# Team_Scheire_Maarten_00.net
KiCad netlist of a schematic drawn in Altium Designer
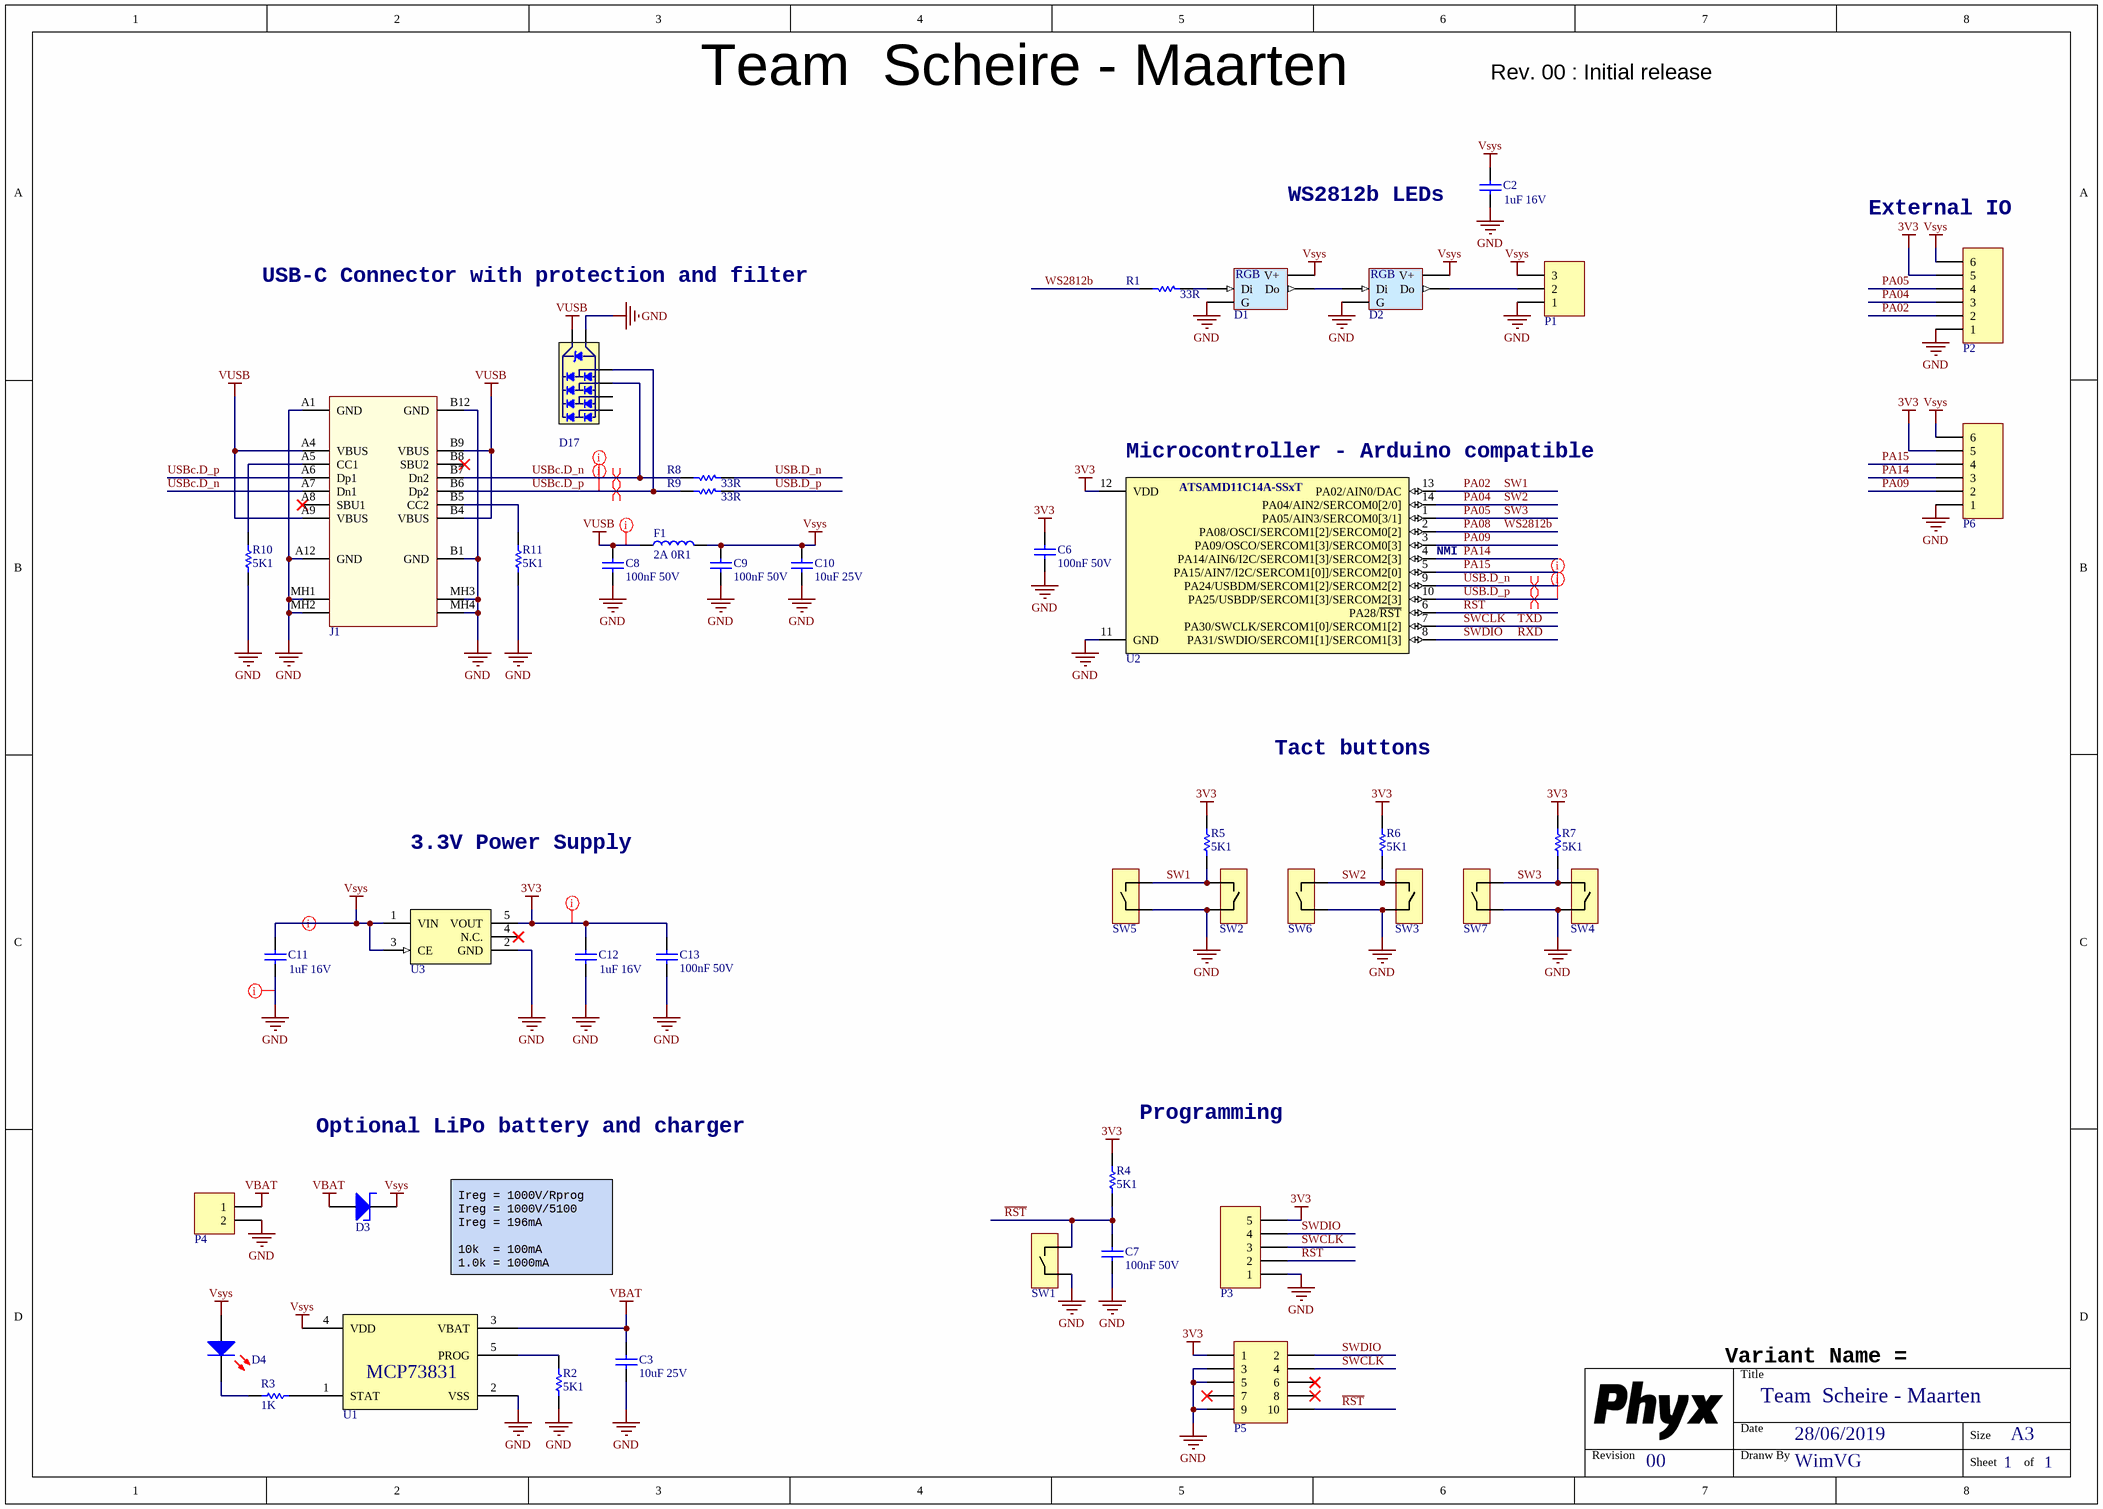
[diagram p0: Team_Scheire_Maarten_00.SchDoc]

(export (version "E")
  (design (tool "Eeschema 10.0.6"))
  (components
    (comp (ref "C2")
      (value "1uF 16V")
      (footprint "C0603_N")
      (description "Capacitor Ceramic")
      (fields (field (name "Comment") "CAP_CERAMIC"))
      (libsource (lib "Phyx_Components") (part "CAP_CERAMIC"))
    )
    (comp (ref "C3")
      (value "10uF 25V")
      (footprint "C1206_N")
      (description "CAP # 10uF 25V 1206")
      (fields (field (name "Comment") "CAP_CERAMIC"))
      (libsource (lib "Phyx_Components") (part "CAP_CERAMIC"))
    )
    (comp (ref "C6")
      (value "100nF 50V")
      (footprint "C0603_N")
      (description "CAP # 100nF 50V 0603")
      (fields (field (name "Comment") "CAP_CERAMIC"))
      (libsource (lib "Phyx_Components") (part "CAP_CERAMIC"))
    )
    (comp (ref "C7")
      (value "100nF 50V")
      (footprint "C0603_N")
      (description "CAP # 100nF 50V 0603")
      (fields (field (name "Comment") "CAP_CERAMIC"))
      (libsource (lib "Phyx_Components") (part "CAP_CERAMIC"))
    )
    (comp (ref "C8")
      (value "100nF 50V")
      (footprint "C0603_N")
      (description "CAP # 100nF 50V 0603")
      (fields (field (name "Comment") "CAP_CERAMIC"))
      (libsource (lib "Phyx_Components") (part "CAP_CERAMIC"))
    )
    (comp (ref "C9")
      (value "100nF 50V")
      (footprint "C0603_N")
      (description "CAP # 100nF 50V 0603")
      (fields (field (name "Comment") "CAP_CERAMIC"))
      (libsource (lib "Phyx_Components") (part "CAP_CERAMIC"))
    )
    (comp (ref "C10")
      (value "10uF 25V")
      (footprint "C1206_N")
      (description "CAP # 10uF 25V 1206")
      (fields (field (name "Comment") "CAP_CERAMIC"))
      (libsource (lib "Phyx_Components") (part "CAP_CERAMIC"))
    )
    (comp (ref "C11")
      (value "1uF 16V")
      (footprint "C0603_N")
      (description "Capacitor Ceramic")
      (fields (field (name "Comment") "CAP_CERAMIC"))
      (libsource (lib "Phyx_Components") (part "CAP_CERAMIC"))
    )
    (comp (ref "C12")
      (value "1uF 16V")
      (footprint "C0603_N")
      (description "Capacitor Ceramic")
      (fields (field (name "Comment") "CAP_CERAMIC"))
      (libsource (lib "Phyx_Components") (part "CAP_CERAMIC"))
    )
    (comp (ref "C13")
      (value "100nF 50V")
      (footprint "C0603_N")
      (description "CAP # 100nF 50V 0603")
      (fields (field (name "Comment") "CAP_CERAMIC"))
      (libsource (lib "Phyx_Components") (part "CAP_CERAMIC"))
    )
    (comp (ref "D1")
      (value "WS2812 based digital RGB LED 5050 Black package")
      (footprint "LED_5050_WS2812B_BLACK")
      (description "=Description")
      (libsource (lib "Phyx_Components") (part "LED_RGB_WS2812B_5050"))
    )
    (comp (ref "D2")
      (value "WS2812 based digital RGB LED 5050 Black package")
      (footprint "LED_5050_WS2812B_BLACK")
      (description "=Description")
      (libsource (lib "Phyx_Components") (part "LED_RGB_WS2812B_5050"))
    )
    (comp (ref "D3")
      (value "MBR0540T3G Schottky ULTRAFAST, 500MA, 40V")
      (footprint "ON_SOD-123FL")
      (description "=Description")
      (libsource (lib "Phyx_Components") (part "Schottky_21"))
    )
    (comp (ref "D4")
      (value "Default 0805 Red LED")
      (footprint "LED_0805_RD")
      (description "=Description")
      (libsource (lib "Phyx_Components") (part "LED_RED"))
    )
    (comp (ref "D17")
      (value "TVS Diode Dual USB")
      (footprint "NXP_SOT457")
      (description "TVS # IP4220CZ6 Dual USB")
      (libsource (lib "Phyx_Components") (part "NXP_IP4220CZ6"))
    )
    (comp (ref "F1")
      (value "2A 0R1")
      (footprint "L0805")
      (fields (field (name "Comment") "FERRITE"))
      (libsource (lib "Phyx_Components") (part "FERRITE"))
    )
    (comp (ref "J1")
      (value "USB 2.0 C Reversible Receptacle Horizontal")
      (footprint "HRO_TYPE-C-31-M-12")
      (libsource (lib "Phyx_Components") (part "USB_C_16_4"))
    )
    (comp (ref "P1")
      (value "Header 2.0mm Shrouded 3")
      (footprint "WE_620103131822")
      (libsource (lib "Phyx_Components") (part "Header 3"))
    )
    (comp (ref "P2")
      (value "Header 6")
      (footprint "HDR1X6")
      (libsource (lib "Phyx_Components") (part "Header 6"))
    )
    (comp (ref "P3")
      (value "Header 1.0mm Shrouded 5")
      (footprint "WE_665305124022")
      (description "HDR # SHR 1.0mm 5way - 665305124022")
      (libsource (lib "Phyx_Components") (part "Header 5"))
    )
    (comp (ref "P4")
      (value "Header 2.0mm Shrouded 2")
      (footprint "WE_620102131822")
      (libsource (lib "Phyx_Components") (part "Header 2"))
    )
    (comp (ref "P5")
      (value "Header 5x2")
      (footprint "HDR2X5_1.27_SMD")
      (libsource (lib "Phyx_Components") (part "Header 5X2"))
    )
    (comp (ref "P6")
      (value "Header 6")
      (footprint "HDR1X6")
      (libsource (lib "Phyx_Components") (part "Header 6"))
    )
    (comp (ref "R1")
      (value "33R")
      (footprint "R0603_N")
      (description "RES # 33R 0603")
      (fields (field (name "Comment") "RESISTOR"))
      (libsource (lib "Phyx_Components") (part "RESISTOR"))
    )
    (comp (ref "R2")
      (value "5K1")
      (footprint "R0603_N")
      (fields (field (name "Comment") "RESISTOR"))
      (libsource (lib "Phyx_Components") (part "RESISTOR"))
    )
    (comp (ref "R3")
      (value "1K")
      (footprint "R0603_N")
      (fields (field (name "Comment") "RESISTOR"))
      (libsource (lib "Phyx_Components") (part "RESISTOR"))
    )
    (comp (ref "R4")
      (value "5K1")
      (footprint "R0603_N")
      (fields (field (name "Comment") "RESISTOR"))
      (libsource (lib "Phyx_Components") (part "RESISTOR"))
    )
    (comp (ref "R5")
      (value "5K1")
      (footprint "R0603_N")
      (fields (field (name "Comment") "RESISTOR"))
      (libsource (lib "Phyx_Components") (part "RESISTOR"))
    )
    (comp (ref "R6")
      (value "5K1")
      (footprint "R0603_N")
      (fields (field (name "Comment") "RESISTOR"))
      (libsource (lib "Phyx_Components") (part "RESISTOR"))
    )
    (comp (ref "R7")
      (value "5K1")
      (footprint "R0603_N")
      (fields (field (name "Comment") "RESISTOR"))
      (libsource (lib "Phyx_Components") (part "RESISTOR"))
    )
    (comp (ref "R8")
      (value "33R")
      (footprint "R0603_N")
      (description "RES # 33R 0603")
      (fields (field (name "Comment") "RESISTOR"))
      (libsource (lib "Phyx_Components") (part "RESISTOR"))
    )
    (comp (ref "R9")
      (value "33R")
      (footprint "R0603_N")
      (description "RES # 33R 0603")
      (fields (field (name "Comment") "RESISTOR"))
      (libsource (lib "Phyx_Components") (part "RESISTOR"))
    )
    (comp (ref "R10")
      (value "5K1")
      (footprint "R0603_N")
      (fields (field (name "Comment") "RESISTOR"))
      (libsource (lib "Phyx_Components") (part "RESISTOR"))
    )
    (comp (ref "R11")
      (value "5K1")
      (footprint "R0603_N")
      (fields (field (name "Comment") "RESISTOR"))
      (libsource (lib "Phyx_Components") (part "RESISTOR"))
    )
    (comp (ref "SW1")
      (value "LP SMD tact sw")
      (footprint "CK_KMR4")
      (libsource (lib "Phyx_Components") (part "SW_TACT"))
    )
    (comp (ref "SW2")
      (value "Tact switch, 12mm, 160g, 7,3mm rect")
      (footprint "ESW_TL3300A")
      (libsource (lib "") (part "SW_TACT_1"))
    )
    (comp (ref "SW3")
      (value "Tact switch, 12mm, 160g, 7,3mm rect")
      (footprint "ESW_TL3300A")
      (libsource (lib "") (part "SW_TACT_1"))
    )
    (comp (ref "SW4")
      (value "Tact switch, 12mm, 160g, 7,3mm rect")
      (footprint "ESW_TL3300A")
      (libsource (lib "") (part "SW_TACT_1"))
    )
    (comp (ref "SW5")
      (value "4.5x4.5mm tact SMD H3,8mm")
      (footprint "WE_430181038816")
      (libsource (lib "Phyx_Components") (part "SW_TACT"))
    )
    (comp (ref "SW6")
      (value "4.5x4.5mm tact SMD H3,8mm")
      (footprint "WE_430181038816")
      (libsource (lib "Phyx_Components") (part "SW_TACT"))
    )
    (comp (ref "SW7")
      (value "4.5x4.5mm tact SMD H3,8mm")
      (footprint "WE_430181038816")
      (libsource (lib "Phyx_Components") (part "SW_TACT"))
    )
    (comp (ref "U1")
      (value "Single Cell LiPo LiIon charger")
      (footprint "SOT23-5")
      (description "=Description")
      (libsource (lib "Phyx_Components") (part "MCP73831_OT"))
    )
    (comp (ref "U2")
      (value "Microchip Atmel SAMD11C14 SOIC14 Cortex-M0 32-bit MCU, 16 KB Flash, 4KB RAM")
      (footprint "SOIC_N_14")
      (libsource (lib "Phyx_Components") (part "ATSAMD11C14A-SSxT"))
    )
    (comp (ref "U3")
      (value "3V3 LDO 700mA 50mV")
      (footprint "SOT23-5")
      (description "=Designator")
      (libsource (lib "Phyx_Components") (part "XC6210_SOT"))
    )
  )
  (nets
    (net (code "1") (name "/PA02") (class "Default")
      (node (ref "P2") (pin "2") (pinfunction "2_2") (pintype "passive"))
      (node (ref "R5") (pin "2") (pinfunction "2_2") (pintype "passive"))
      (node (ref "SW2") (pin "1") (pinfunction "1_1") (pintype "passive"))
      (node (ref "SW5") (pin "1") (pinfunction "1_1") (pintype "passive"))
      (node (ref "U2") (pin "13") (pinfunction "PA02/AIN0/DAC_13") (pintype "bidirectional"))
    )
    (net (code "2") (name "/PA04") (class "Default")
      (node (ref "P2") (pin "3") (pinfunction "3_3") (pintype "passive"))
      (node (ref "R6") (pin "2") (pinfunction "2_2") (pintype "passive"))
      (node (ref "SW3") (pin "1") (pinfunction "1_1") (pintype "passive"))
      (node (ref "SW6") (pin "1") (pinfunction "1_1") (pintype "passive"))
      (node (ref "U2") (pin "14") (pinfunction "PA04/AIN2/SERCOM0[2/0]_14") (pintype "bidirectional"))
    )
    (net (code "3") (name "/PA05") (class "Default")
      (node (ref "P2") (pin "4") (pinfunction "4_4") (pintype "passive"))
      (node (ref "R7") (pin "2") (pinfunction "2_2") (pintype "passive"))
      (node (ref "SW4") (pin "1") (pinfunction "1_1") (pintype "passive"))
      (node (ref "SW7") (pin "1") (pinfunction "1_1") (pintype "passive"))
      (node (ref "U2") (pin "1") (pinfunction "PA05/AIN3/SERCOM0[3/1]_1") (pintype "bidirectional"))
    )
    (net (code "4") (name "/PA08") (class "Default")
      (node (ref "R1") (pin "1") (pinfunction "1_1") (pintype "passive"))
      (node (ref "U2") (pin "2") (pinfunction "PA08/OSCI/SERCOM1[2]/SERCOM0[2]_2") (pintype "bidirectional"))
    )
    (net (code "5") (name "/PA09") (class "Default")
      (node (ref "P6") (pin "2") (pinfunction "2_2") (pintype "passive"))
      (node (ref "U2") (pin "3") (pinfunction "PA09/OSCO/SERCOM1[3]/SERCOM0[3]_3") (pintype "bidirectional"))
    )
    (net (code "6") (name "/PA14") (class "Default")
      (node (ref "P6") (pin "3") (pinfunction "3_3") (pintype "passive"))
      (node (ref "U2") (pin "4") (pinfunction "PA14/AIN6/I2C/SERCOM1[3]/SERCOM2[3]_4") (pintype "bidirectional"))
    )
    (net (code "7") (name "/PA15") (class "Default")
      (node (ref "P6") (pin "4") (pinfunction "4_4") (pintype "passive"))
      (node (ref "U2") (pin "5") (pinfunction "PA15/AIN7/I2C/SERCOM1[0]]/SERCOM2[0]_5") (pintype "bidirectional"))
    )
    (net (code "8") (name "/RXD") (class "Default")
      (node (ref "P3") (pin "4") (pinfunction "4_4") (pintype "passive"))
      (node (ref "P5") (pin "2") (pinfunction "2_2") (pintype "passive"))
      (node (ref "U2") (pin "8") (pinfunction "PA31/SWDIO/SERCOM1[1]/SERCOM1[3]_8") (pintype "bidirectional"))
    )
    (net (code "9") (name "/SWCLK") (class "Default")
      (node (ref "P3") (pin "3") (pinfunction "3_3") (pintype "passive"))
      (node (ref "P5") (pin "4") (pinfunction "4_4") (pintype "passive"))
      (node (ref "U2") (pin "7") (pinfunction "PA30/SWCLK/SERCOM1[0]/SERCOM1[2]_7") (pintype "bidirectional"))
    )
    (net (code "10") (name "/USB.D_n") (class "Default")
      (node (ref "R8") (pin "2") (pinfunction "2_2") (pintype "passive"))
      (node (ref "U2") (pin "9") (pinfunction "PA24/USBDM/SERCOM1[2]/SERCOM2[2]_9") (pintype "bidirectional"))
    )
    (net (code "11") (name "/USB.D_p") (class "Default")
      (node (ref "R9") (pin "2") (pinfunction "2_2") (pintype "passive"))
      (node (ref "U2") (pin "10") (pinfunction "PA25/USBDP/SERCOM1[3]/SERCOM2[3]_10") (pintype "bidirectional"))
    )
    (net (code "12") (name "/USBc.D_n") (class "Default")
      (node (ref "D17") (pin "1") (pinfunction "1_1") (pintype "passive"))
      (node (ref "J1") (pin "A7") (pinfunction "Dn1_A7") (pintype "passive"))
      (node (ref "J1") (pin "B7") (pinfunction "Dn2_B7") (pintype "passive"))
      (node (ref "R8") (pin "1") (pinfunction "1_1") (pintype "passive"))
    )
    (net (code "13") (name "/USBc.D_p") (class "Default")
      (node (ref "D17") (pin "3") (pinfunction "3_3") (pintype "passive"))
      (node (ref "J1") (pin "A6") (pinfunction "Dp1_A6") (pintype "passive"))
      (node (ref "J1") (pin "B6") (pinfunction "Dp2_B6") (pintype "passive"))
      (node (ref "R9") (pin "1") (pinfunction "1_1") (pintype "passive"))
    )
    (net (code "14") (name "/~{RST}") (class "Default")
      (node (ref "C7") (pin "1") (pinfunction "1_1") (pintype "passive"))
      (node (ref "P3") (pin "2") (pinfunction "2_2") (pintype "passive"))
      (node (ref "P5") (pin "10") (pinfunction "10_10") (pintype "passive"))
      (node (ref "R4") (pin "2") (pinfunction "2_2") (pintype "passive"))
      (node (ref "SW1") (pin "1") (pinfunction "1_1") (pintype "passive"))
      (node (ref "U2") (pin "6") (pinfunction "PA28/~{RST}_6") (pintype "bidirectional"))
    )
    (net (code "15") (name "3V3") (class "Default")
      (node (ref "C12") (pin "1") (pinfunction "1_1") (pintype "passive"))
      (node (ref "C13") (pin "1") (pinfunction "1_1") (pintype "passive"))
      (node (ref "C6") (pin "1") (pinfunction "1_1") (pintype "passive"))
      (node (ref "P2") (pin "5") (pinfunction "5_5") (pintype "passive"))
      (node (ref "P3") (pin "5") (pinfunction "5_5") (pintype "passive"))
      (node (ref "P5") (pin "1") (pinfunction "1_1") (pintype "passive"))
      (node (ref "P6") (pin "5") (pinfunction "5_5") (pintype "passive"))
      (node (ref "R4") (pin "1") (pinfunction "1_1") (pintype "passive"))
      (node (ref "R5") (pin "1") (pinfunction "1_1") (pintype "passive"))
      (node (ref "R6") (pin "1") (pinfunction "1_1") (pintype "passive"))
      (node (ref "R7") (pin "1") (pinfunction "1_1") (pintype "passive"))
      (node (ref "U2") (pin "12") (pinfunction "VDD_12") (pintype "power_in"))
      (node (ref "U3") (pin "5") (pinfunction "VOUT_5") (pintype "power_in"))
    )
    (net (code "16") (name "GND") (class "Default")
      (node (ref "C10") (pin "2") (pinfunction "2_2") (pintype "passive"))
      (node (ref "C11") (pin "2") (pinfunction "2_2") (pintype "passive"))
      (node (ref "C12") (pin "2") (pinfunction "2_2") (pintype "passive"))
      (node (ref "C13") (pin "2") (pinfunction "2_2") (pintype "passive"))
      (node (ref "C2") (pin "2") (pinfunction "2_2") (pintype "passive"))
      (node (ref "C3") (pin "2") (pinfunction "2_2") (pintype "passive"))
      (node (ref "C6") (pin "2") (pinfunction "2_2") (pintype "passive"))
      (node (ref "C7") (pin "2") (pinfunction "2_2") (pintype "passive"))
      (node (ref "C8") (pin "2") (pinfunction "2_2") (pintype "passive"))
      (node (ref "C9") (pin "2") (pinfunction "2_2") (pintype "passive"))
      (node (ref "D1") (pin "3") (pinfunction "G_3") (pintype "power_in"))
      (node (ref "D17") (pin "2") (pinfunction "GND_2") (pintype "passive"))
      (node (ref "D2") (pin "3") (pinfunction "G_3") (pintype "power_in"))
      (node (ref "J1") (pin "A1") (pinfunction "GND_A1") (pintype "passive"))
      (node (ref "J1") (pin "A12") (pinfunction "GND_A12") (pintype "passive"))
      (node (ref "J1") (pin "B1") (pinfunction "GND_B1") (pintype "passive"))
      (node (ref "J1") (pin "B12") (pinfunction "GND_B12") (pintype "passive"))
      (node (ref "J1") (pin "MH1") (pinfunction "Tab_MH1") (pintype "passive"))
      (node (ref "J1") (pin "MH2") (pinfunction "Tab_MH2") (pintype "passive"))
      (node (ref "J1") (pin "MH3") (pinfunction "Tab_MH3") (pintype "passive"))
      (node (ref "J1") (pin "MH4") (pinfunction "Tab_MH4") (pintype "passive"))
      (node (ref "P1") (pin "1") (pinfunction "1_1") (pintype "passive"))
      (node (ref "P2") (pin "1") (pinfunction "1_1") (pintype "passive"))
      (node (ref "P3") (pin "1") (pinfunction "1_1") (pintype "passive"))
      (node (ref "P4") (pin "2") (pinfunction "2_2") (pintype "passive"))
      (node (ref "P5") (pin "3") (pinfunction "3_3") (pintype "passive"))
      (node (ref "P5") (pin "5") (pinfunction "5_5") (pintype "passive"))
      (node (ref "P5") (pin "9") (pinfunction "9_9") (pintype "passive"))
      (node (ref "P6") (pin "1") (pinfunction "1_1") (pintype "passive"))
      (node (ref "R10") (pin "2") (pinfunction "2_2") (pintype "passive"))
      (node (ref "R11") (pin "2") (pinfunction "2_2") (pintype "passive"))
      (node (ref "R2") (pin "2") (pinfunction "2_2") (pintype "passive"))
      (node (ref "SW1") (pin "2") (pinfunction "2_2") (pintype "passive"))
      (node (ref "SW2") (pin "2") (pinfunction "2_2") (pintype "passive"))
      (node (ref "SW3") (pin "2") (pinfunction "2_2") (pintype "passive"))
      (node (ref "SW4") (pin "2") (pinfunction "2_2") (pintype "passive"))
      (node (ref "SW5") (pin "2") (pinfunction "2_2") (pintype "passive"))
      (node (ref "SW6") (pin "2") (pinfunction "2_2") (pintype "passive"))
      (node (ref "SW7") (pin "2") (pinfunction "2_2") (pintype "passive"))
      (node (ref "U1") (pin "2") (pinfunction "VSS_2") (pintype "power_in"))
      (node (ref "U2") (pin "11") (pinfunction "GND_11") (pintype "power_in"))
      (node (ref "U3") (pin "2") (pinfunction "GND_2") (pintype "power_in"))
    )
    (net (code "17") (name "Net-(D1-Di)") (class "Default")
      (node (ref "D1") (pin "4") (pinfunction "Di_4") (pintype "input"))
      (node (ref "R1") (pin "2") (pinfunction "2_2") (pintype "passive"))
    )
    (net (code "18") (name "Net-(D1-Do)") (class "Default")
      (node (ref "D1") (pin "2") (pinfunction "Do_2") (pintype "output"))
      (node (ref "D2") (pin "4") (pinfunction "Di_4") (pintype "input"))
    )
    (net (code "19") (name "Net-(D2-Do)") (class "Default")
      (node (ref "D2") (pin "2") (pinfunction "Do_2") (pintype "output"))
      (node (ref "P1") (pin "2") (pinfunction "2_2") (pintype "passive"))
    )
    (net (code "20") (name "Net-(D4-K)") (class "Default")
      (node (ref "D4") (pin "2") (pinfunction "K_2") (pintype "passive"))
      (node (ref "R3") (pin "2") (pinfunction "2_2") (pintype "passive"))
    )
    (net (code "21") (name "Net-(J1-CC1)") (class "Default")
      (node (ref "J1") (pin "A5") (pinfunction "CC1_A5") (pintype "passive"))
      (node (ref "R10") (pin "1") (pinfunction "1_1") (pintype "passive"))
    )
    (net (code "22") (name "Net-(J1-CC2)") (class "Default")
      (node (ref "J1") (pin "B5") (pinfunction "CC2_B5") (pintype "passive"))
      (node (ref "R11") (pin "1") (pinfunction "1_1") (pintype "passive"))
    )
    (net (code "23") (name "Net-(U1-PROG)") (class "Default")
      (node (ref "R2") (pin "1") (pinfunction "1_1") (pintype "passive"))
      (node (ref "U1") (pin "5") (pinfunction "PROG_5") (pintype "passive"))
    )
    (net (code "24") (name "Net-(U1-STAT)") (class "Default")
      (node (ref "R3") (pin "1") (pinfunction "1_1") (pintype "passive"))
      (node (ref "U1") (pin "1") (pinfunction "STAT_1") (pintype "passive"))
    )
    (net (code "25") (name "VBAT") (class "Default")
      (node (ref "C3") (pin "1") (pinfunction "1_1") (pintype "passive"))
      (node (ref "D3") (pin "2") (pinfunction "A_2") (pintype "passive"))
      (node (ref "P4") (pin "1") (pinfunction "1_1") (pintype "passive"))
      (node (ref "U1") (pin "3") (pinfunction "VBAT_3") (pintype "power_in"))
    )
    (net (code "26") (name "VUSB") (class "Default")
      (node (ref "C8") (pin "1") (pinfunction "1_1") (pintype "passive"))
      (node (ref "D17") (pin "5") (pinfunction "VBus_5") (pintype "passive"))
      (node (ref "F1") (pin "1") (pinfunction "1_1") (pintype "passive"))
      (node (ref "J1") (pin "A4") (pinfunction "VBUS_A4") (pintype "passive"))
      (node (ref "J1") (pin "A9") (pinfunction "VBUS_A9") (pintype "passive"))
      (node (ref "J1") (pin "B4") (pinfunction "VBUS_B4") (pintype "passive"))
      (node (ref "J1") (pin "B9") (pinfunction "VBUS_B9") (pintype "passive"))
    )
    (net (code "27") (name "Vsys") (class "Default")
      (node (ref "C10") (pin "1") (pinfunction "1_1") (pintype "passive"))
      (node (ref "C11") (pin "1") (pinfunction "1_1") (pintype "passive"))
      (node (ref "C2") (pin "1") (pinfunction "1_1") (pintype "passive"))
      (node (ref "C9") (pin "1") (pinfunction "1_1") (pintype "passive"))
      (node (ref "D1") (pin "1") (pinfunction "V+_1") (pintype "power_in"))
      (node (ref "D2") (pin "1") (pinfunction "V+_1") (pintype "power_in"))
      (node (ref "D3") (pin "1") (pinfunction "C_1") (pintype "passive"))
      (node (ref "D4") (pin "1") (pinfunction "A_1") (pintype "passive"))
      (node (ref "F1") (pin "2") (pinfunction "2_2") (pintype "passive"))
      (node (ref "P1") (pin "3") (pinfunction "3_3") (pintype "passive"))
      (node (ref "P2") (pin "6") (pinfunction "6_6") (pintype "passive"))
      (node (ref "P6") (pin "6") (pinfunction "6_6") (pintype "passive"))
      (node (ref "U1") (pin "4") (pinfunction "VDD_4") (pintype "power_in"))
      (node (ref "U3") (pin "1") (pinfunction "VIN_1") (pintype "power_in"))
      (node (ref "U3") (pin "3") (pinfunction "CE_3") (pintype "input"))
    )
    (net (code "28") (name "unconnected-(D17-Pad4)") (class "Default")
      (node (ref "D17") (pin "4") (pinfunction "4_4") (pintype "passive"))
    )
    (net (code "29") (name "unconnected-(D17-Pad6)") (class "Default")
      (node (ref "D17") (pin "6") (pinfunction "6_6") (pintype "passive"))
    )
    (net (code "30") (name "unconnected-(J1-SBU1-PadA8)") (class "Default")
      (node (ref "J1") (pin "A8") (pinfunction "SBU1_A8") (pintype "passive+no_connect"))
    )
    (net (code "31") (name "unconnected-(J1-SBU2-PadB8)") (class "Default")
      (node (ref "J1") (pin "B8") (pinfunction "SBU2_B8") (pintype "passive+no_connect"))
    )
    (net (code "32") (name "unconnected-(P5-Pad6)") (class "Default")
      (node (ref "P5") (pin "6") (pinfunction "6_6") (pintype "passive+no_connect"))
    )
    (net (code "33") (name "unconnected-(P5-Pad7)") (class "Default")
      (node (ref "P5") (pin "7") (pinfunction "7_7") (pintype "passive+no_connect"))
    )
    (net (code "34") (name "unconnected-(P5-Pad8)") (class "Default")
      (node (ref "P5") (pin "8") (pinfunction "8_8") (pintype "passive+no_connect"))
    )
    (net (code "35") (name "unconnected-(U3-N.C.-Pad4)") (class "Default")
      (node (ref "U3") (pin "4") (pinfunction "N.C._4") (pintype "passive+no_connect"))
    )
  )
)
